# BME680.net
KiCad netlist of a schematic drawn in Altium Designer
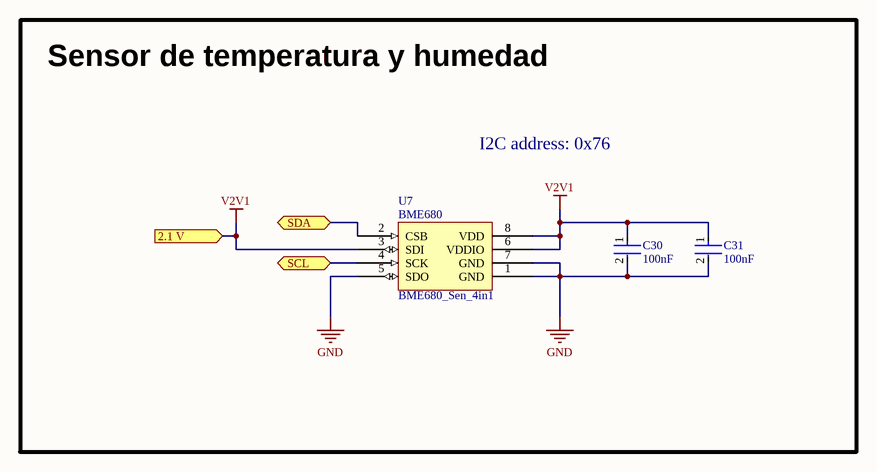
[diagram p0: BME680.SchDoc]

(export (version "E")
  (design (tool "Eeschema 10.0.6"))
  (components
    (comp (ref "C30")
      (value "100nF")
      (footprint "FP-CL10-IPC_B")
      (description "Cap Ceramic 10uF 10V X5R ±10% Pad SMD 0603 +85°C T/R")
      (fields (field (name "TOLERANCE") "10%"))
      (libsource (lib "Altium Content Vault") (part "b4654b650e69147ec39a6b967a45e02"))
    )
    (comp (ref "C31")
      (value "100nF")
      (footprint "FP-CL10-IPC_B")
      (description "Cap Ceramic 10uF 10V X5R ±10% Pad SMD 0603 +85°C T/R")
      (fields (field (name "TOLERANCE") "10%"))
      (libsource (lib "Altium Content Vault") (part "b4654b650e69147ec39a6b967a45e02"))
    )
    (comp (ref "U7")
      (value "BME680_Sen_4in1")
      (footprint "BME_LGA8")
      (libsource (lib "DEOP2021") (part "BME680_Sen_4in1"))
    )
  )
  (nets
    (net (code "1") (name "/SCL") (class "Default")
      (node (ref "U7") (pin "4") (pinfunction "SCK_4") (pintype "input"))
    )
    (net (code "2") (name "/SDA") (class "Default")
      (node (ref "U7") (pin "2") (pinfunction "CSB_2") (pintype "input"))
    )
    (net (code "3") (name "GND") (class "Default")
      (node (ref "C30") (pin "2") (pinfunction "2_2") (pintype "passive"))
      (node (ref "C31") (pin "2") (pinfunction "2_2") (pintype "passive"))
      (node (ref "U7") (pin "1") (pinfunction "GND_1") (pintype "power_in"))
      (node (ref "U7") (pin "5") (pinfunction "SDO_5") (pintype "bidirectional"))
      (node (ref "U7") (pin "7") (pinfunction "GND_7") (pintype "power_in"))
    )
    (net (code "4") (name "V2V1") (class "Default")
      (node (ref "C30") (pin "1") (pinfunction "1_1") (pintype "passive"))
      (node (ref "C31") (pin "1") (pinfunction "1_1") (pintype "passive"))
      (node (ref "U7") (pin "3") (pinfunction "SDI_3") (pintype "bidirectional"))
      (node (ref "U7") (pin "6") (pinfunction "VDDIO_6") (pintype "power_in"))
      (node (ref "U7") (pin "8") (pinfunction "VDD_8") (pintype "power_in"))
    )
  )
)
